# mcu_v051.net
KiCad netlist of a schematic drawn in EAGLE
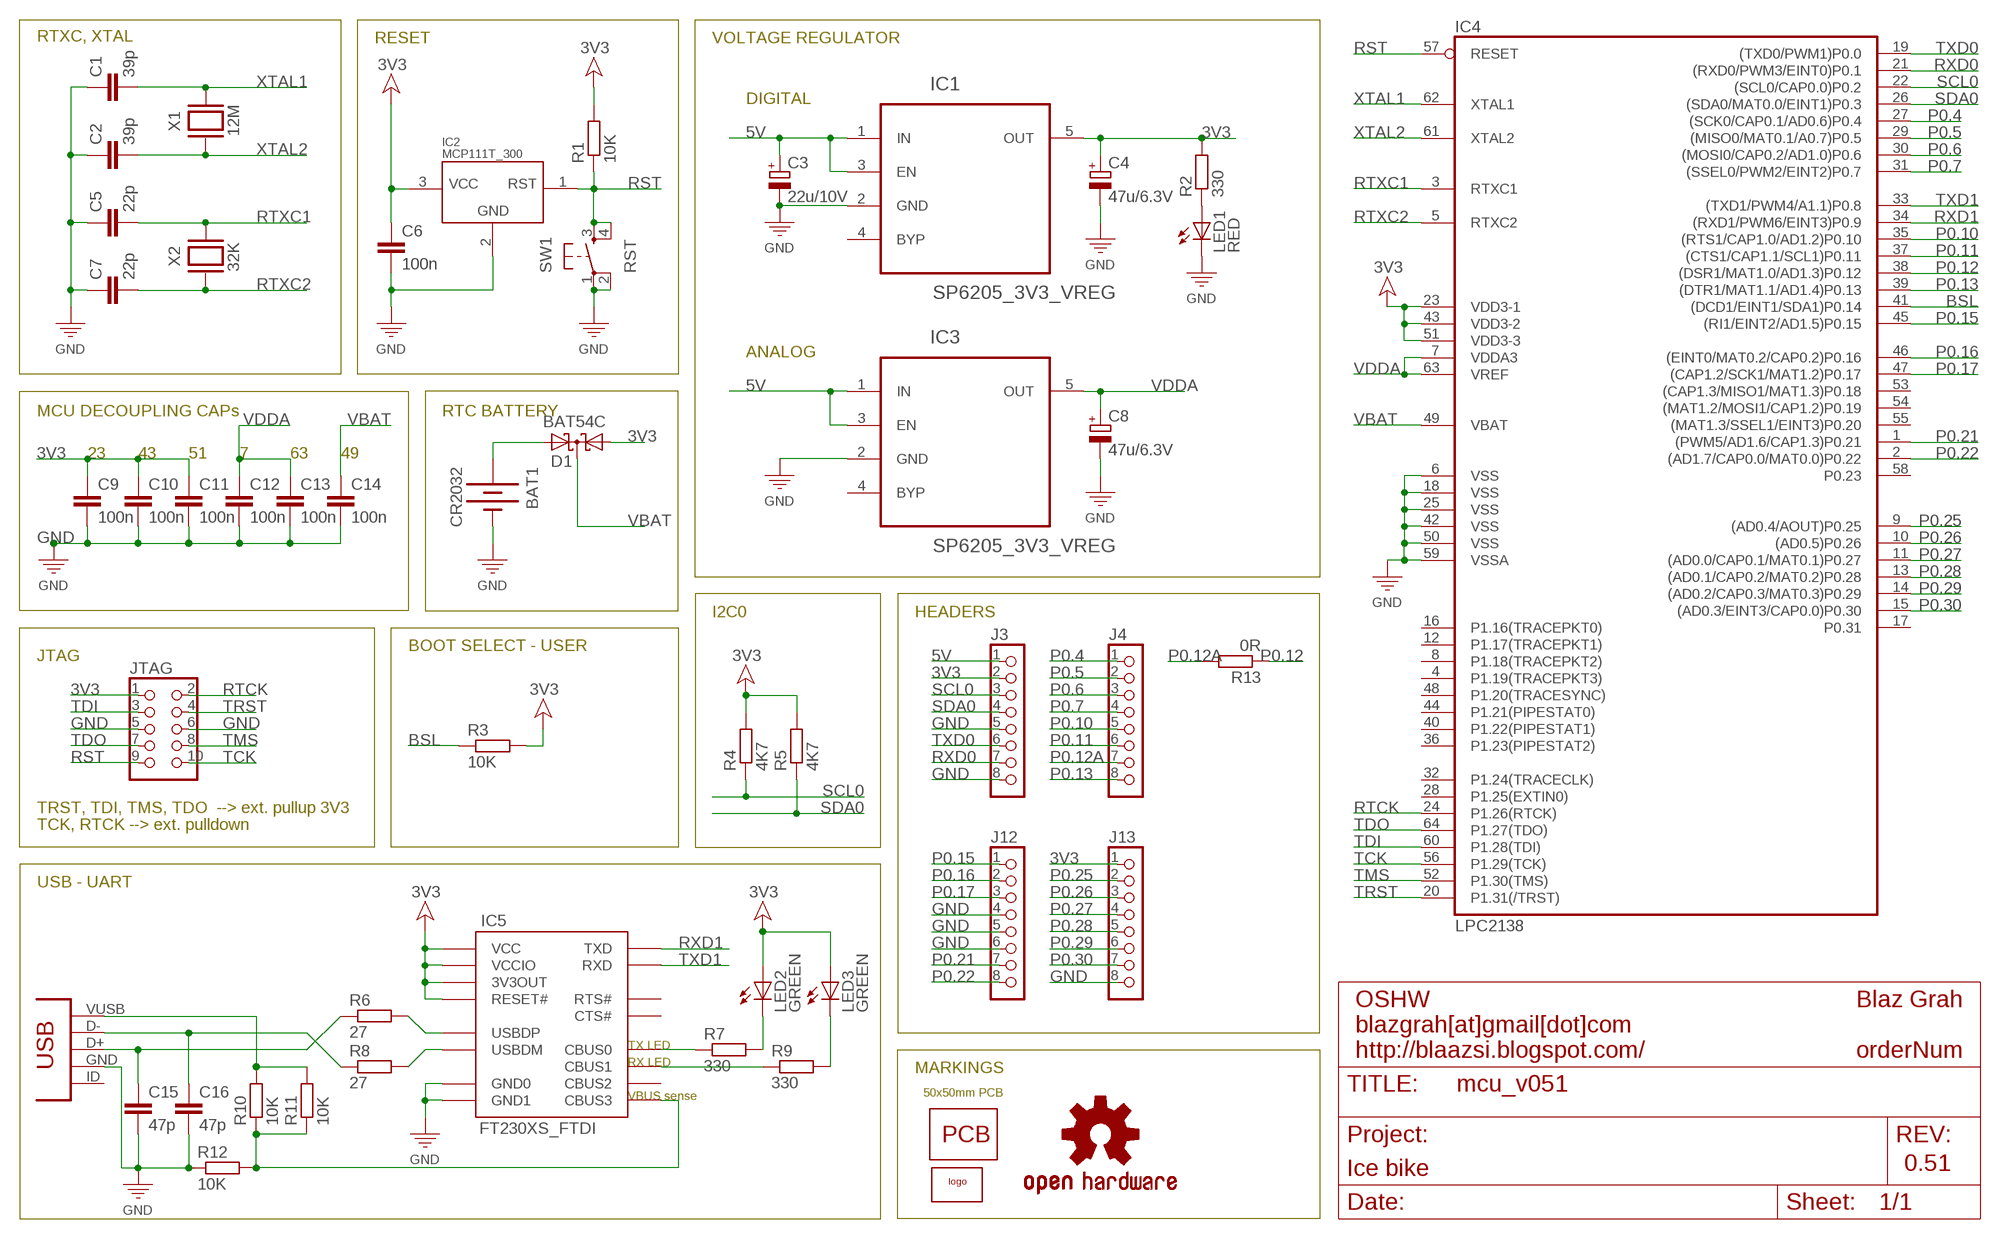
[diagram p0: schematic, sheet 1]

(export (version "E")
  (design (tool "Eeschema 10.0.6"))
  (components
    (comp (ref "BAT1")
      (value "CR2032")
      (footprint "eagle-import:BATTERY_20MM_SMD")
      (libsource (lib "eagle-import") (part "BATTERY20MM"))
    )
    (comp (ref "C1")
      (value "39p")
      (footprint "eagle-import:C0603")
      (libsource (lib "eagle-import") (part "C-EUC0603"))
    )
    (comp (ref "C2")
      (value "39p")
      (footprint "eagle-import:C0603")
      (libsource (lib "eagle-import") (part "C-EUC0603"))
    )
    (comp (ref "C3")
      (value "22u/10V")
      (footprint "eagle-import:SMC_B")
      (libsource (lib "eagle-import") (part "CAPACITOR_POL-SMC_B"))
    )
    (comp (ref "C4")
      (value "47u/6.3V")
      (footprint "eagle-import:SMC_B")
      (libsource (lib "eagle-import") (part "CAPACITOR_POL-SMC_B"))
    )
    (comp (ref "C5")
      (value "22p")
      (footprint "eagle-import:C0603")
      (libsource (lib "eagle-import") (part "C-EUC0603"))
    )
    (comp (ref "C6")
      (value "100n")
      (footprint "eagle-import:C0603")
      (libsource (lib "eagle-import") (part "C-EUC0603"))
    )
    (comp (ref "C7")
      (value "22p")
      (footprint "eagle-import:C0603")
      (libsource (lib "eagle-import") (part "C-EUC0603"))
    )
    (comp (ref "C8")
      (value "47u/6.3V")
      (footprint "eagle-import:SMC_B")
      (libsource (lib "eagle-import") (part "CAPACITOR_POL-SMC_B"))
    )
    (comp (ref "C9")
      (value "100n")
      (footprint "eagle-import:C0603")
      (libsource (lib "eagle-import") (part "C-EUC0603"))
    )
    (comp (ref "C10")
      (value "100n")
      (footprint "eagle-import:C0603")
      (libsource (lib "eagle-import") (part "C-EUC0603"))
    )
    (comp (ref "C11")
      (value "100n")
      (footprint "eagle-import:C0603")
      (libsource (lib "eagle-import") (part "C-EUC0603"))
    )
    (comp (ref "C12")
      (value "100n")
      (footprint "eagle-import:C0603")
      (libsource (lib "eagle-import") (part "C-EUC0603"))
    )
    (comp (ref "C13")
      (value "100n")
      (footprint "eagle-import:C0603")
      (libsource (lib "eagle-import") (part "C-EUC0603"))
    )
    (comp (ref "C14")
      (value "100n")
      (footprint "eagle-import:C0603")
      (libsource (lib "eagle-import") (part "C-EUC0603"))
    )
    (comp (ref "C15")
      (value "47p")
      (footprint "eagle-import:C0603")
      (libsource (lib "eagle-import") (part "C-EUC0603"))
    )
    (comp (ref "C16")
      (value "47p")
      (footprint "eagle-import:C0603")
      (libsource (lib "eagle-import") (part "C-EUC0603"))
    )
    (comp (ref "D1")
      (value "BAT54C")
      (footprint "eagle-import:SOT23")
      (libsource (lib "eagle-import") (part "BAT54C"))
    )
    (comp (ref "DOC")
      (value "FRAME_DINA4_L")
      (footprint "eagle-import:DP_LOGO")
      (fields
        (field (name "AUTHOR") "Blaz Grah")
        (field (name "DATE") "23.4.2012")
        (field (name "LICENSE") "OSHW")
        (field (name "PROJECT") "Ice bike")
        (field (name "REV") "0.51")
        (field (name "URL1") "blazgrah[at]gmail[dot]com")
        (field (name "URL2") "http://blaazsi.blogspot.com/")
      )
      (libsource (lib "eagle-import") (part "FRAME_DINA4_L"))
    )
    (comp (ref "IC1")
      (value "SP6205_3V3_VREG")
      (footprint "eagle-import:SOT23-5")
      (libsource (lib "eagle-import") (part "SP6205_3V3_VREG"))
    )
    (comp (ref "IC2")
      (value "MCP111T_300")
      (footprint "eagle-import:SOT23")
      (libsource (lib "eagle-import") (part "MCP111T_300"))
    )
    (comp (ref "IC3")
      (value "SP6205_3V3_VREG")
      (footprint "eagle-import:SOT23-5")
      (libsource (lib "eagle-import") (part "SP6205_3V3_VREG"))
    )
    (comp (ref "IC4")
      (value "LPC2138")
      (footprint "eagle-import:LQFP64")
      (libsource (lib "eagle-import") (part "LCP2138_LQFP64"))
    )
    (comp (ref "IC5")
      (value "FT230XS_FTDI")
      (footprint "eagle-import:SSOP16")
      (libsource (lib "eagle-import") (part "FT230XS_FTDI"))
    )
    (comp (ref "J3")
      (value "CON_HEADER_1X08-PTH")
      (footprint "eagle-import:M1X8")
      (libsource (lib "eagle-import") (part "CON_HEADER_1X08-PTH"))
    )
    (comp (ref "J4")
      (value "CON_HEADER_1X08-PTH")
      (footprint "eagle-import:M1X8")
      (libsource (lib "eagle-import") (part "CON_HEADER_1X08-PTH"))
    )
    (comp (ref "J12")
      (value "CON_HEADER_1X08-PTH")
      (footprint "eagle-import:M1X8")
      (libsource (lib "eagle-import") (part "CON_HEADER_1X08-PTH"))
    )
    (comp (ref "J13")
      (value "CON_HEADER_1X08-PTH")
      (footprint "eagle-import:M1X8")
      (libsource (lib "eagle-import") (part "CON_HEADER_1X08-PTH"))
    )
    (comp (ref "JTAG")
      (value "CON_HEADER_2X05-PTH+SHROUDED_A")
      (footprint "eagle-import:PINSHRD_PTH_2X05")
      (libsource (lib "eagle-import") (part "CON_HEADER_2X05-PTH+SHROUDED_A"))
    )
    (comp (ref "LED1")
      (value "RED")
      (footprint "eagle-import:LED0805")
      (libsource (lib "eagle-import") (part "LED0805"))
    )
    (comp (ref "LED2")
      (value "GREEN")
      (footprint "eagle-import:LED0805")
      (libsource (lib "eagle-import") (part "LED0805"))
    )
    (comp (ref "LED3")
      (value "GREEN")
      (footprint "eagle-import:LED0805")
      (libsource (lib "eagle-import") (part "LED0805"))
    )
    (comp (ref "LOGO1")
      (value "OSHW-LOGOS")
      (footprint "eagle-import:OSHW-LOGO-S")
      (libsource (lib "eagle-import") (part "OSHW-LOGOS"))
    )
    (comp (ref "PCB1")
      (value "PCB")
      (footprint "eagle-import:PCB_50X50")
      (libsource (lib "eagle-import") (part "PCB"))
    )
    (comp (ref "R1")
      (value "10K")
      (footprint "eagle-import:R0603")
      (libsource (lib "eagle-import") (part "R-EU0603"))
    )
    (comp (ref "R2")
      (value "330")
      (footprint "eagle-import:R0603")
      (libsource (lib "eagle-import") (part "R-EU0603"))
    )
    (comp (ref "R3")
      (value "10K")
      (footprint "eagle-import:R0603")
      (libsource (lib "eagle-import") (part "R-EU0603"))
    )
    (comp (ref "R4")
      (value "4K7")
      (footprint "eagle-import:R0603")
      (libsource (lib "eagle-import") (part "R-EU0603"))
    )
    (comp (ref "R5")
      (value "4K7")
      (footprint "eagle-import:R0603")
      (libsource (lib "eagle-import") (part "R-EU0603"))
    )
    (comp (ref "R6")
      (value "27")
      (footprint "eagle-import:R0603")
      (libsource (lib "eagle-import") (part "R-EU0603"))
    )
    (comp (ref "R7")
      (value "330")
      (footprint "eagle-import:R0603")
      (libsource (lib "eagle-import") (part "R-EU0603"))
    )
    (comp (ref "R8")
      (value "27")
      (footprint "eagle-import:R0603")
      (libsource (lib "eagle-import") (part "R-EU0603"))
    )
    (comp (ref "R9")
      (value "330")
      (footprint "eagle-import:R0603")
      (libsource (lib "eagle-import") (part "R-EU0603"))
    )
    (comp (ref "R10")
      (value "10K")
      (footprint "eagle-import:R0603")
      (libsource (lib "eagle-import") (part "R-EU0603"))
    )
    (comp (ref "R11")
      (value "10K")
      (footprint "eagle-import:R0603")
      (libsource (lib "eagle-import") (part "R-EU0603"))
    )
    (comp (ref "R12")
      (value "10K")
      (footprint "eagle-import:R0603")
      (libsource (lib "eagle-import") (part "R-EU0603"))
    )
    (comp (ref "R13")
      (value "0R")
      (footprint "eagle-import:R0603_JUMP")
      (libsource (lib "eagle-import") (part "R-EU0603J"))
    )
    (comp (ref "SW1")
      (value "RST")
      (footprint "eagle-import:BUTTON_SW_4P_SMD")
      (libsource (lib "eagle-import") (part "TACTIL_BUTTON"))
    )
    (comp (ref "U$13")
      (value "LOGO")
      (footprint "eagle-import:LOGO_SMILE")
      (libsource (lib "eagle-import") (part "LOGO"))
    )
    (comp (ref "USB1")
      (value "CON-USB-F-MINI-B")
      (footprint "eagle-import:CONN_USB_MINI-B")
      (libsource (lib "eagle-import") (part "CON-USB-F-MINI-B"))
    )
    (comp (ref "X1")
      (value "12M")
      (footprint "eagle-import:CRYSTAL_12M_4.8X10.6MM")
      (libsource (lib "eagle-import") (part "CRYSTALSMD_4.8X10.6"))
    )
    (comp (ref "X2")
      (value "32K")
      (footprint "eagle-import:CRYSTAL_32K_SMD")
      (libsource (lib "eagle-import") (part "CRYSTALSMD_32K"))
    )
  )
  (nets
    (net (code "1") (name "/5V") (class "Default")
      (node (ref "C3") (pin "+") (pinfunction "+_+") (pintype "passive"))
      (node (ref "IC1") (pin "1") (pinfunction "IN_1") (pintype "input"))
      (node (ref "IC1") (pin "3") (pinfunction "EN_3") (pintype "input"))
      (node (ref "IC3") (pin "1") (pinfunction "IN_1") (pintype "input"))
      (node (ref "IC3") (pin "3") (pinfunction "EN_3") (pintype "input"))
      (node (ref "J3") (pin "1") (pinfunction "1_1") (pintype "passive"))
    )
    (net (code "2") (name "/BSL") (class "Default")
      (node (ref "IC4") (pin "41") (pinfunction "(DCD1/EINT1/SDA1)P0.14_41") (pintype "bidirectional"))
      (node (ref "R3") (pin "1") (pinfunction "1_1") (pintype "passive"))
    )
    (net (code "3") (name "/P0.4") (class "Default")
      (node (ref "IC4") (pin "27") (pinfunction "(SCK0/CAP0.1/AD0.6)P0.4_27") (pintype "bidirectional"))
      (node (ref "J4") (pin "1") (pinfunction "1_1") (pintype "passive"))
    )
    (net (code "4") (name "/P0.5") (class "Default")
      (node (ref "IC4") (pin "29") (pinfunction "(MISO0/MAT0.1/A0.7)P0.5_29") (pintype "bidirectional"))
      (node (ref "J4") (pin "2") (pinfunction "2_2") (pintype "passive"))
    )
    (net (code "5") (name "/P0.6") (class "Default")
      (node (ref "IC4") (pin "30") (pinfunction "(MOSI0/CAP0.2/AD1.0)P0.6_30") (pintype "bidirectional"))
      (node (ref "J4") (pin "3") (pinfunction "3_3") (pintype "passive"))
    )
    (net (code "6") (name "/P0.7") (class "Default")
      (node (ref "IC4") (pin "31") (pinfunction "(SSEL0/PWM2/EINT2)P0.7_31") (pintype "bidirectional"))
      (node (ref "J4") (pin "4") (pinfunction "4_4") (pintype "passive"))
    )
    (net (code "7") (name "/P0.10") (class "Default")
      (node (ref "IC4") (pin "35") (pinfunction "(RTS1/CAP1.0/AD1.2)P0.10_35") (pintype "bidirectional"))
      (node (ref "J4") (pin "5") (pinfunction "5_5") (pintype "passive"))
    )
    (net (code "8") (name "/P0.11") (class "Default")
      (node (ref "IC4") (pin "37") (pinfunction "(CTS1/CAP1.1/SCL1)P0.11_37") (pintype "bidirectional"))
      (node (ref "J4") (pin "6") (pinfunction "6_6") (pintype "passive"))
    )
    (net (code "9") (name "/P0.12") (class "Default")
      (node (ref "IC4") (pin "38") (pinfunction "(DSR1/MAT1.0/AD1.3)P0.12_38") (pintype "bidirectional"))
      (node (ref "R13") (pin "1") (pinfunction "1_1") (pintype "passive"))
    )
    (net (code "10") (name "/P0.12A") (class "Default")
      (node (ref "J4") (pin "7") (pinfunction "7_7") (pintype "passive"))
      (node (ref "R13") (pin "2") (pinfunction "2_2") (pintype "passive"))
    )
    (net (code "11") (name "/P0.13") (class "Default")
      (node (ref "IC4") (pin "39") (pinfunction "(DTR1/MAT1.1/AD1.4)P0.13_39") (pintype "bidirectional"))
      (node (ref "J4") (pin "8") (pinfunction "8_8") (pintype "passive"))
    )
    (net (code "12") (name "/P0.15") (class "Default")
      (node (ref "IC4") (pin "45") (pinfunction "(RI1/EINT2/AD1.5)P0.15_45") (pintype "bidirectional"))
      (node (ref "J12") (pin "1") (pinfunction "1_1") (pintype "passive"))
    )
    (net (code "13") (name "/P0.16") (class "Default")
      (node (ref "IC4") (pin "46") (pinfunction "(EINT0/MAT0.2/CAP0.2)P0.16_46") (pintype "bidirectional"))
      (node (ref "J12") (pin "2") (pinfunction "2_2") (pintype "passive"))
    )
    (net (code "14") (name "/P0.17") (class "Default")
      (node (ref "IC4") (pin "47") (pinfunction "(CAP1.2/SCK1/MAT1.2)P0.17_47") (pintype "bidirectional"))
      (node (ref "J12") (pin "3") (pinfunction "3_3") (pintype "passive"))
    )
    (net (code "15") (name "/P0.21") (class "Default")
      (node (ref "IC4") (pin "1") (pinfunction "(PWM5/AD1.6/CAP1.3)P0.21_1") (pintype "bidirectional"))
      (node (ref "J12") (pin "7") (pinfunction "7_7") (pintype "passive"))
    )
    (net (code "16") (name "/P0.22") (class "Default")
      (node (ref "IC4") (pin "2") (pinfunction "(AD1.7/CAP0.0/MAT0.0)P0.22_2") (pintype "bidirectional"))
      (node (ref "J12") (pin "8") (pinfunction "8_8") (pintype "passive"))
    )
    (net (code "17") (name "/P0.25") (class "Default")
      (node (ref "IC4") (pin "9") (pinfunction "(AD0.4/AOUT)P0.25_9") (pintype "bidirectional"))
      (node (ref "J13") (pin "2") (pinfunction "2_2") (pintype "passive"))
    )
    (net (code "18") (name "/P0.26") (class "Default")
      (node (ref "IC4") (pin "10") (pinfunction "(AD0.5)P0.26_10") (pintype "bidirectional"))
      (node (ref "J13") (pin "3") (pinfunction "3_3") (pintype "passive"))
    )
    (net (code "19") (name "/P0.27") (class "Default")
      (node (ref "IC4") (pin "11") (pinfunction "(AD0.0/CAP0.1/MAT0.1)P0.27_11") (pintype "bidirectional"))
      (node (ref "J13") (pin "4") (pinfunction "4_4") (pintype "passive"))
    )
    (net (code "20") (name "/P0.28") (class "Default")
      (node (ref "IC4") (pin "13") (pinfunction "(AD0.1/CAP0.2/MAT0.2)P0.28_13") (pintype "bidirectional"))
      (node (ref "J13") (pin "5") (pinfunction "5_5") (pintype "passive"))
    )
    (net (code "21") (name "/P0.29") (class "Default")
      (node (ref "IC4") (pin "14") (pinfunction "(AD0.2/CAP0.3/MAT0.3)P0.29_14") (pintype "bidirectional"))
      (node (ref "J13") (pin "6") (pinfunction "6_6") (pintype "passive"))
    )
    (net (code "22") (name "/P0.30") (class "Default")
      (node (ref "IC4") (pin "15") (pinfunction "(AD0.3/EINT3/CAP0.0)P0.30_15") (pintype "bidirectional"))
      (node (ref "J13") (pin "7") (pinfunction "7_7") (pintype "passive"))
    )
    (net (code "23") (name "/RST") (class "Default")
      (node (ref "IC2") (pin "1") (pinfunction "RST_1") (pintype "output"))
      (node (ref "IC4") (pin "57") (pinfunction "RESET_57") (pintype "input"))
      (node (ref "JTAG") (pin "9") (pinfunction "9_9") (pintype "passive"))
      (node (ref "R1") (pin "1") (pinfunction "1_1") (pintype "passive"))
      (node (ref "SW1") (pin "3") (pinfunction "3_3") (pintype "passive"))
      (node (ref "SW1") (pin "4") (pinfunction "4_4") (pintype "passive"))
    )
    (net (code "24") (name "/RTCK") (class "Default")
      (node (ref "IC4") (pin "24") (pinfunction "P1.26(RTCK)_24") (pintype "bidirectional"))
      (node (ref "JTAG") (pin "2") (pinfunction "2_2") (pintype "passive"))
    )
    (net (code "25") (name "/RTXC1") (class "Default")
      (node (ref "C5") (pin "2") (pinfunction "2_2") (pintype "passive"))
      (node (ref "IC4") (pin "3") (pinfunction "RTXC1_3") (pintype "input"))
      (node (ref "X2") (pin "X2") (pinfunction "2_X2") (pintype "passive"))
    )
    (net (code "26") (name "/RTXC2") (class "Default")
      (node (ref "C7") (pin "2") (pinfunction "2_2") (pintype "passive"))
      (node (ref "IC4") (pin "5") (pinfunction "RTXC2_5") (pintype "output"))
      (node (ref "X2") (pin "X1") (pinfunction "1_X1") (pintype "passive"))
    )
    (net (code "27") (name "/RXD0") (class "Default")
      (node (ref "IC4") (pin "21") (pinfunction "(RXD0/PWM3/EINT0)P0.1_21") (pintype "bidirectional"))
      (node (ref "J3") (pin "7") (pinfunction "7_7") (pintype "passive"))
    )
    (net (code "28") (name "/RXD1") (class "Default")
      (node (ref "IC4") (pin "34") (pinfunction "(RXD1/PWM6/EINT3)P0.9_34") (pintype "bidirectional"))
      (node (ref "IC5") (pin "P$1") (pinfunction "TXD_P$1") (pintype "bidirectional"))
    )
    (net (code "29") (name "/SCL0") (class "Default")
      (node (ref "IC4") (pin "22") (pinfunction "(SCL0/CAP0.0)P0.2_22") (pintype "bidirectional"))
      (node (ref "J3") (pin "3") (pinfunction "3_3") (pintype "passive"))
      (node (ref "R4") (pin "1") (pinfunction "1_1") (pintype "passive"))
    )
    (net (code "30") (name "/SDA0") (class "Default")
      (node (ref "IC4") (pin "26") (pinfunction "(SDA0/MAT0.0/EINT1)P0.3_26") (pintype "bidirectional"))
      (node (ref "J3") (pin "4") (pinfunction "4_4") (pintype "passive"))
      (node (ref "R5") (pin "1") (pinfunction "1_1") (pintype "passive"))
    )
    (net (code "31") (name "/TCK") (class "Default")
      (node (ref "IC4") (pin "56") (pinfunction "P1.29(TCK)_56") (pintype "bidirectional"))
      (node (ref "JTAG") (pin "10") (pinfunction "10_10") (pintype "passive"))
    )
    (net (code "32") (name "/TDI") (class "Default")
      (node (ref "IC4") (pin "60") (pinfunction "P1.28(TDI)_60") (pintype "bidirectional"))
      (node (ref "JTAG") (pin "3") (pinfunction "3_3") (pintype "passive"))
    )
    (net (code "33") (name "/TDO") (class "Default")
      (node (ref "IC4") (pin "64") (pinfunction "P1.27(TDO)_64") (pintype "bidirectional"))
      (node (ref "JTAG") (pin "7") (pinfunction "7_7") (pintype "passive"))
    )
    (net (code "34") (name "/TMS") (class "Default")
      (node (ref "IC4") (pin "52") (pinfunction "P1.30(TMS)_52") (pintype "bidirectional"))
      (node (ref "JTAG") (pin "8") (pinfunction "8_8") (pintype "passive"))
    )
    (net (code "35") (name "/TRST") (class "Default")
      (node (ref "IC4") (pin "20") (pinfunction "P1.31(/TRST)_20") (pintype "bidirectional"))
      (node (ref "JTAG") (pin "4") (pinfunction "4_4") (pintype "passive"))
    )
    (net (code "36") (name "/TXD0") (class "Default")
      (node (ref "IC4") (pin "19") (pinfunction "(TXD0/PWM1)P0.0_19") (pintype "bidirectional"))
      (node (ref "J3") (pin "6") (pinfunction "6_6") (pintype "passive"))
    )
    (net (code "37") (name "/TXD1") (class "Default")
      (node (ref "IC4") (pin "33") (pinfunction "(TXD1/PWM4/A1.1)P0.8_33") (pintype "bidirectional"))
      (node (ref "IC5") (pin "P$4") (pinfunction "RXD_P$4") (pintype "bidirectional"))
    )
    (net (code "38") (name "/VBAT") (class "Default")
      (node (ref "C14") (pin "1") (pinfunction "1_1") (pintype "passive"))
      (node (ref "D1") (pin "3") (pinfunction "CC_3") (pintype "passive"))
      (node (ref "IC4") (pin "49") (pinfunction "VBAT_49") (pintype "power_in"))
    )
    (net (code "39") (name "/VDDA") (class "Default")
      (node (ref "C12") (pin "1") (pinfunction "1_1") (pintype "passive"))
      (node (ref "C13") (pin "1") (pinfunction "1_1") (pintype "passive"))
      (node (ref "C8") (pin "+") (pinfunction "+_+") (pintype "passive"))
      (node (ref "IC3") (pin "5") (pinfunction "OUT_5") (pintype "power_in"))
      (node (ref "IC4") (pin "63") (pinfunction "VREF_63") (pintype "input"))
      (node (ref "IC4") (pin "7") (pinfunction "VDDA3_7") (pintype "power_in"))
    )
    (net (code "40") (name "/XTAL1") (class "Default")
      (node (ref "C1") (pin "2") (pinfunction "2_2") (pintype "passive"))
      (node (ref "IC4") (pin "62") (pinfunction "XTAL1_62") (pintype "input"))
      (node (ref "X1") (pin "P$2") (pinfunction "2_P$2") (pintype "passive"))
    )
    (net (code "41") (name "/XTAL2") (class "Default")
      (node (ref "C2") (pin "2") (pinfunction "2_2") (pintype "passive"))
      (node (ref "IC4") (pin "61") (pinfunction "XTAL2_61") (pintype "output"))
      (node (ref "X1") (pin "P$1") (pinfunction "1_P$1") (pintype "passive"))
    )
    (net (code "42") (name "3V3") (class "Default")
      (node (ref "C10") (pin "1") (pinfunction "1_1") (pintype "passive"))
      (node (ref "C11") (pin "1") (pinfunction "1_1") (pintype "passive"))
      (node (ref "C4") (pin "+") (pinfunction "+_+") (pintype "passive"))
      (node (ref "C6") (pin "1") (pinfunction "1_1") (pintype "passive"))
      (node (ref "C9") (pin "1") (pinfunction "1_1") (pintype "passive"))
      (node (ref "D1") (pin "1") (pinfunction "A1_1") (pintype "passive"))
      (node (ref "IC1") (pin "5") (pinfunction "OUT_5") (pintype "power_in"))
      (node (ref "IC2") (pin "3") (pinfunction "VCC_3") (pintype "input"))
      (node (ref "IC4") (pin "23") (pinfunction "VDD3-1_23") (pintype "power_in"))
      (node (ref "IC4") (pin "43") (pinfunction "VDD3-2_43") (pintype "power_in"))
      (node (ref "IC4") (pin "51") (pinfunction "VDD3-3_51") (pintype "power_in"))
      (node (ref "IC5") (pin "P$10") (pinfunction "3V3OUT_P$10") (pintype "power_in"))
      (node (ref "IC5") (pin "P$11") (pinfunction "RESET#_P$11") (pintype "bidirectional"))
      (node (ref "IC5") (pin "P$12") (pinfunction "VCC_P$12") (pintype "power_in"))
      (node (ref "IC5") (pin "P$3") (pinfunction "VCCIO_P$3") (pintype "power_in"))
      (node (ref "J13") (pin "1") (pinfunction "1_1") (pintype "passive"))
      (node (ref "J3") (pin "2") (pinfunction "2_2") (pintype "passive"))
      (node (ref "JTAG") (pin "1") (pinfunction "1_1") (pintype "passive"))
      (node (ref "LED2") (pin "A") (pinfunction "A_A") (pintype "passive"))
      (node (ref "LED3") (pin "A") (pinfunction "A_A") (pintype "passive"))
      (node (ref "R1") (pin "2") (pinfunction "2_2") (pintype "passive"))
      (node (ref "R2") (pin "2") (pinfunction "2_2") (pintype "passive"))
      (node (ref "R3") (pin "2") (pinfunction "2_2") (pintype "passive"))
      (node (ref "R4") (pin "2") (pinfunction "2_2") (pintype "passive"))
      (node (ref "R5") (pin "2") (pinfunction "2_2") (pintype "passive"))
    )
    (net (code "43") (name "GND") (class "Default")
      (node (ref "BAT1") (pin "NEG") (pinfunction "NEG_NEG") (pintype "power_in"))
      (node (ref "C1") (pin "1") (pinfunction "1_1") (pintype "passive"))
      (node (ref "C10") (pin "2") (pinfunction "2_2") (pintype "passive"))
      (node (ref "C11") (pin "2") (pinfunction "2_2") (pintype "passive"))
      (node (ref "C12") (pin "2") (pinfunction "2_2") (pintype "passive"))
      (node (ref "C13") (pin "2") (pinfunction "2_2") (pintype "passive"))
      (node (ref "C14") (pin "2") (pinfunction "2_2") (pintype "passive"))
      (node (ref "C15") (pin "2") (pinfunction "2_2") (pintype "passive"))
      (node (ref "C16") (pin "2") (pinfunction "2_2") (pintype "passive"))
      (node (ref "C2") (pin "1") (pinfunction "1_1") (pintype "passive"))
      (node (ref "C3") (pin "-") (pinfunction "-_-") (pintype "passive"))
      (node (ref "C4") (pin "-") (pinfunction "-_-") (pintype "passive"))
      (node (ref "C5") (pin "1") (pinfunction "1_1") (pintype "passive"))
      (node (ref "C6") (pin "2") (pinfunction "2_2") (pintype "passive"))
      (node (ref "C7") (pin "1") (pinfunction "1_1") (pintype "passive"))
      (node (ref "C8") (pin "-") (pinfunction "-_-") (pintype "passive"))
      (node (ref "C9") (pin "2") (pinfunction "2_2") (pintype "passive"))
      (node (ref "IC1") (pin "2") (pinfunction "GND_2") (pintype "power_in"))
      (node (ref "IC2") (pin "2") (pinfunction "GND_2") (pintype "power_in"))
      (node (ref "IC3") (pin "2") (pinfunction "GND_2") (pintype "power_in"))
      (node (ref "IC4") (pin "18") (pinfunction "VSS_18") (pintype "power_in"))
      (node (ref "IC4") (pin "25") (pinfunction "VSS_25") (pintype "power_in"))
      (node (ref "IC4") (pin "42") (pinfunction "VSS_42") (pintype "power_in"))
      (node (ref "IC4") (pin "50") (pinfunction "VSS_50") (pintype "power_in"))
      (node (ref "IC4") (pin "59") (pinfunction "VSSA_59") (pintype "power_in"))
      (node (ref "IC4") (pin "6") (pinfunction "VSS_6") (pintype "power_in"))
      (node (ref "IC5") (pin "P$13") (pinfunction "GND1_P$13") (pintype "power_in"))
      (node (ref "IC5") (pin "P$5") (pinfunction "GND0_P$5") (pintype "power_in"))
      (node (ref "J12") (pin "4") (pinfunction "4_4") (pintype "passive"))
      (node (ref "J12") (pin "5") (pinfunction "5_5") (pintype "passive"))
      (node (ref "J12") (pin "6") (pinfunction "6_6") (pintype "passive"))
      (node (ref "J13") (pin "8") (pinfunction "8_8") (pintype "passive"))
      (node (ref "J3") (pin "5") (pinfunction "5_5") (pintype "passive"))
      (node (ref "J3") (pin "8") (pinfunction "8_8") (pintype "passive"))
      (node (ref "JTAG") (pin "5") (pinfunction "5_5") (pintype "passive"))
      (node (ref "JTAG") (pin "6") (pinfunction "6_6") (pintype "passive"))
      (node (ref "LED1") (pin "C") (pinfunction "C_C") (pintype "passive"))
      (node (ref "R12") (pin "1") (pinfunction "1_1") (pintype "passive"))
      (node (ref "SW1") (pin "1") (pinfunction "1_1") (pintype "passive"))
      (node (ref "SW1") (pin "2") (pinfunction "2_2") (pintype "passive"))
      (node (ref "USB1") (pin "GND") (pinfunction "GND_GND") (pintype "bidirectional"))
    )
    (net (code "44") (name "Net-(C15-Pad1)") (class "Default")
      (node (ref "C15") (pin "1") (pinfunction "1_1") (pintype "passive"))
      (node (ref "R6") (pin "1") (pinfunction "1_1") (pintype "passive"))
      (node (ref "USB1") (pin "D+") (pinfunction "D+_D+") (pintype "bidirectional"))
    )
    (net (code "45") (name "Net-(C16-Pad1)") (class "Default")
      (node (ref "C16") (pin "1") (pinfunction "1_1") (pintype "passive"))
      (node (ref "R8") (pin "1") (pinfunction "1_1") (pintype "passive"))
      (node (ref "USB1") (pin "D-") (pinfunction "D-_D-") (pintype "bidirectional"))
    )
    (net (code "46") (name "Net-(D1-A2)") (class "Default")
      (node (ref "BAT1") (pin "POS1") (pinfunction "POZ_POS1") (pintype "power_in"))
      (node (ref "BAT1") (pin "POS2") (pinfunction "POZ_POS2") (pintype "power_in"))
      (node (ref "D1") (pin "2") (pinfunction "A2_2") (pintype "passive"))
    )
    (net (code "47") (name "Net-(IC5-CBUS0)") (class "Default")
      (node (ref "IC5") (pin "P$15") (pinfunction "CBUS0_P$15") (pintype "bidirectional"))
      (node (ref "R7") (pin "1") (pinfunction "1_1") (pintype "passive"))
    )
    (net (code "48") (name "Net-(IC5-CBUS1)") (class "Default")
      (node (ref "IC5") (pin "P$14") (pinfunction "CBUS1_P$14") (pintype "bidirectional"))
      (node (ref "R9") (pin "1") (pinfunction "1_1") (pintype "passive"))
    )
    (net (code "49") (name "Net-(IC5-CBUS3)") (class "Default")
      (node (ref "IC5") (pin "P$16") (pinfunction "CBUS3_P$16") (pintype "bidirectional"))
      (node (ref "R10") (pin "1") (pinfunction "1_1") (pintype "passive"))
      (node (ref "R11") (pin "1") (pinfunction "1_1") (pintype "passive"))
      (node (ref "R12") (pin "2") (pinfunction "2_2") (pintype "passive"))
    )
    (net (code "50") (name "Net-(IC5-USBDM)") (class "Default")
      (node (ref "IC5") (pin "P$9") (pinfunction "USBDM_P$9") (pintype "bidirectional"))
      (node (ref "R8") (pin "2") (pinfunction "2_2") (pintype "passive"))
    )
    (net (code "51") (name "Net-(IC5-USBDP)") (class "Default")
      (node (ref "IC5") (pin "P$8") (pinfunction "USBDP_P$8") (pintype "bidirectional"))
      (node (ref "R6") (pin "2") (pinfunction "2_2") (pintype "passive"))
    )
    (net (code "52") (name "Net-(LED1-PadA)") (class "Default")
      (node (ref "LED1") (pin "A") (pinfunction "A_A") (pintype "passive"))
      (node (ref "R2") (pin "1") (pinfunction "1_1") (pintype "passive"))
    )
    (net (code "53") (name "Net-(LED2-PadC)") (class "Default")
      (node (ref "LED2") (pin "C") (pinfunction "C_C") (pintype "passive"))
      (node (ref "R7") (pin "2") (pinfunction "2_2") (pintype "passive"))
    )
    (net (code "54") (name "Net-(LED3-PadC)") (class "Default")
      (node (ref "LED3") (pin "C") (pinfunction "C_C") (pintype "passive"))
      (node (ref "R9") (pin "2") (pinfunction "2_2") (pintype "passive"))
    )
    (net (code "55") (name "Net-(R10-Pad2)") (class "Default")
      (node (ref "R10") (pin "2") (pinfunction "2_2") (pintype "passive"))
      (node (ref "R11") (pin "2") (pinfunction "2_2") (pintype "passive"))
      (node (ref "USB1") (pin "VUSB") (pinfunction "VUSB_VUSB") (pintype "bidirectional"))
    )
    (net (code "56") (name "unconnected-(IC1-BYP-Pad4)") (class "Default")
      (node (ref "IC1") (pin "4") (pinfunction "BYP_4") (pintype "no_connect"))
    )
    (net (code "57") (name "unconnected-(IC3-BYP-Pad4)") (class "Default")
      (node (ref "IC3") (pin "4") (pinfunction "BYP_4") (pintype "no_connect"))
    )
    (net (code "58") (name "unconnected-(IC4-(CAP1.3{slash}MISO1{slash}MAT1.3)P0.18-Pad53)") (class "Default")
      (node (ref "IC4") (pin "53") (pinfunction "(CAP1.3/MISO1/MAT1.3)P0.18_53") (pintype "bidirectional"))
    )
    (net (code "59") (name "unconnected-(IC4-(MAT1.2{slash}MOSI1{slash}CAP1.2)P0.19-Pad54)") (class "Default")
      (node (ref "IC4") (pin "54") (pinfunction "(MAT1.2/MOSI1/CAP1.2)P0.19_54") (pintype "bidirectional"))
    )
    (net (code "60") (name "unconnected-(IC4-(MAT1.3{slash}SSEL1{slash}EINT3)P0.20-Pad55)") (class "Default")
      (node (ref "IC4") (pin "55") (pinfunction "(MAT1.3/SSEL1/EINT3)P0.20_55") (pintype "bidirectional"))
    )
    (net (code "61") (name "unconnected-(IC4-P0.23-Pad58)") (class "Default")
      (node (ref "IC4") (pin "58") (pinfunction "P0.23_58") (pintype "bidirectional"))
    )
    (net (code "62") (name "unconnected-(IC4-P0.31-Pad17)") (class "Default")
      (node (ref "IC4") (pin "17") (pinfunction "P0.31_17") (pintype "output"))
    )
    (net (code "63") (name "unconnected-(IC4-P1.16(TRACEPKT0)-Pad16)") (class "Default")
      (node (ref "IC4") (pin "16") (pinfunction "P1.16(TRACEPKT0)_16") (pintype "bidirectional"))
    )
    (net (code "64") (name "unconnected-(IC4-P1.17(TRACEPKT1)-Pad12)") (class "Default")
      (node (ref "IC4") (pin "12") (pinfunction "P1.17(TRACEPKT1)_12") (pintype "bidirectional"))
    )
    (net (code "65") (name "unconnected-(IC4-P1.18(TRACEPKT2)-Pad8)") (class "Default")
      (node (ref "IC4") (pin "8") (pinfunction "P1.18(TRACEPKT2)_8") (pintype "bidirectional"))
    )
    (net (code "66") (name "unconnected-(IC4-P1.19(TRACEPKT3)-Pad4)") (class "Default")
      (node (ref "IC4") (pin "4") (pinfunction "P1.19(TRACEPKT3)_4") (pintype "bidirectional"))
    )
    (net (code "67") (name "unconnected-(IC4-P1.20(TRACESYNC)-Pad48)") (class "Default")
      (node (ref "IC4") (pin "48") (pinfunction "P1.20(TRACESYNC)_48") (pintype "bidirectional"))
    )
    (net (code "68") (name "unconnected-(IC4-P1.21(PIPESTAT0)-Pad44)") (class "Default")
      (node (ref "IC4") (pin "44") (pinfunction "P1.21(PIPESTAT0)_44") (pintype "bidirectional"))
    )
    (net (code "69") (name "unconnected-(IC4-P1.22(PIPESTAT1)-Pad40)") (class "Default")
      (node (ref "IC4") (pin "40") (pinfunction "P1.22(PIPESTAT1)_40") (pintype "bidirectional"))
    )
    (net (code "70") (name "unconnected-(IC4-P1.23(PIPESTAT2)-Pad36)") (class "Default")
      (node (ref "IC4") (pin "36") (pinfunction "P1.23(PIPESTAT2)_36") (pintype "bidirectional"))
    )
    (net (code "71") (name "unconnected-(IC4-P1.24(TRACECLK)-Pad32)") (class "Default")
      (node (ref "IC4") (pin "32") (pinfunction "P1.24(TRACECLK)_32") (pintype "bidirectional"))
    )
    (net (code "72") (name "unconnected-(IC4-P1.25(EXTIN0)-Pad28)") (class "Default")
      (node (ref "IC4") (pin "28") (pinfunction "P1.25(EXTIN0)_28") (pintype "bidirectional"))
    )
    (net (code "73") (name "unconnected-(IC5-CBUS2-PadP$7)") (class "Default")
      (node (ref "IC5") (pin "P$7") (pinfunction "CBUS2_P$7") (pintype "bidirectional"))
    )
    (net (code "74") (name "unconnected-(IC5-CTS#-PadP$6)") (class "Default")
      (node (ref "IC5") (pin "P$6") (pinfunction "CTS#_P$6") (pintype "bidirectional"))
    )
    (net (code "75") (name "unconnected-(IC5-RTS#-PadP$2)") (class "Default")
      (node (ref "IC5") (pin "P$2") (pinfunction "RTS#_P$2") (pintype "bidirectional"))
    )
    (net (code "76") (name "unconnected-(USB1B-USBID-PadID)") (class "Default")
      (node (ref "USB1") (pin "ID") (pinfunction "USBID_ID") (pintype "bidirectional"))
    )
  )
)
